# BigBus_Error.net
KiCad netlist of a schematic drawn in EAGLE
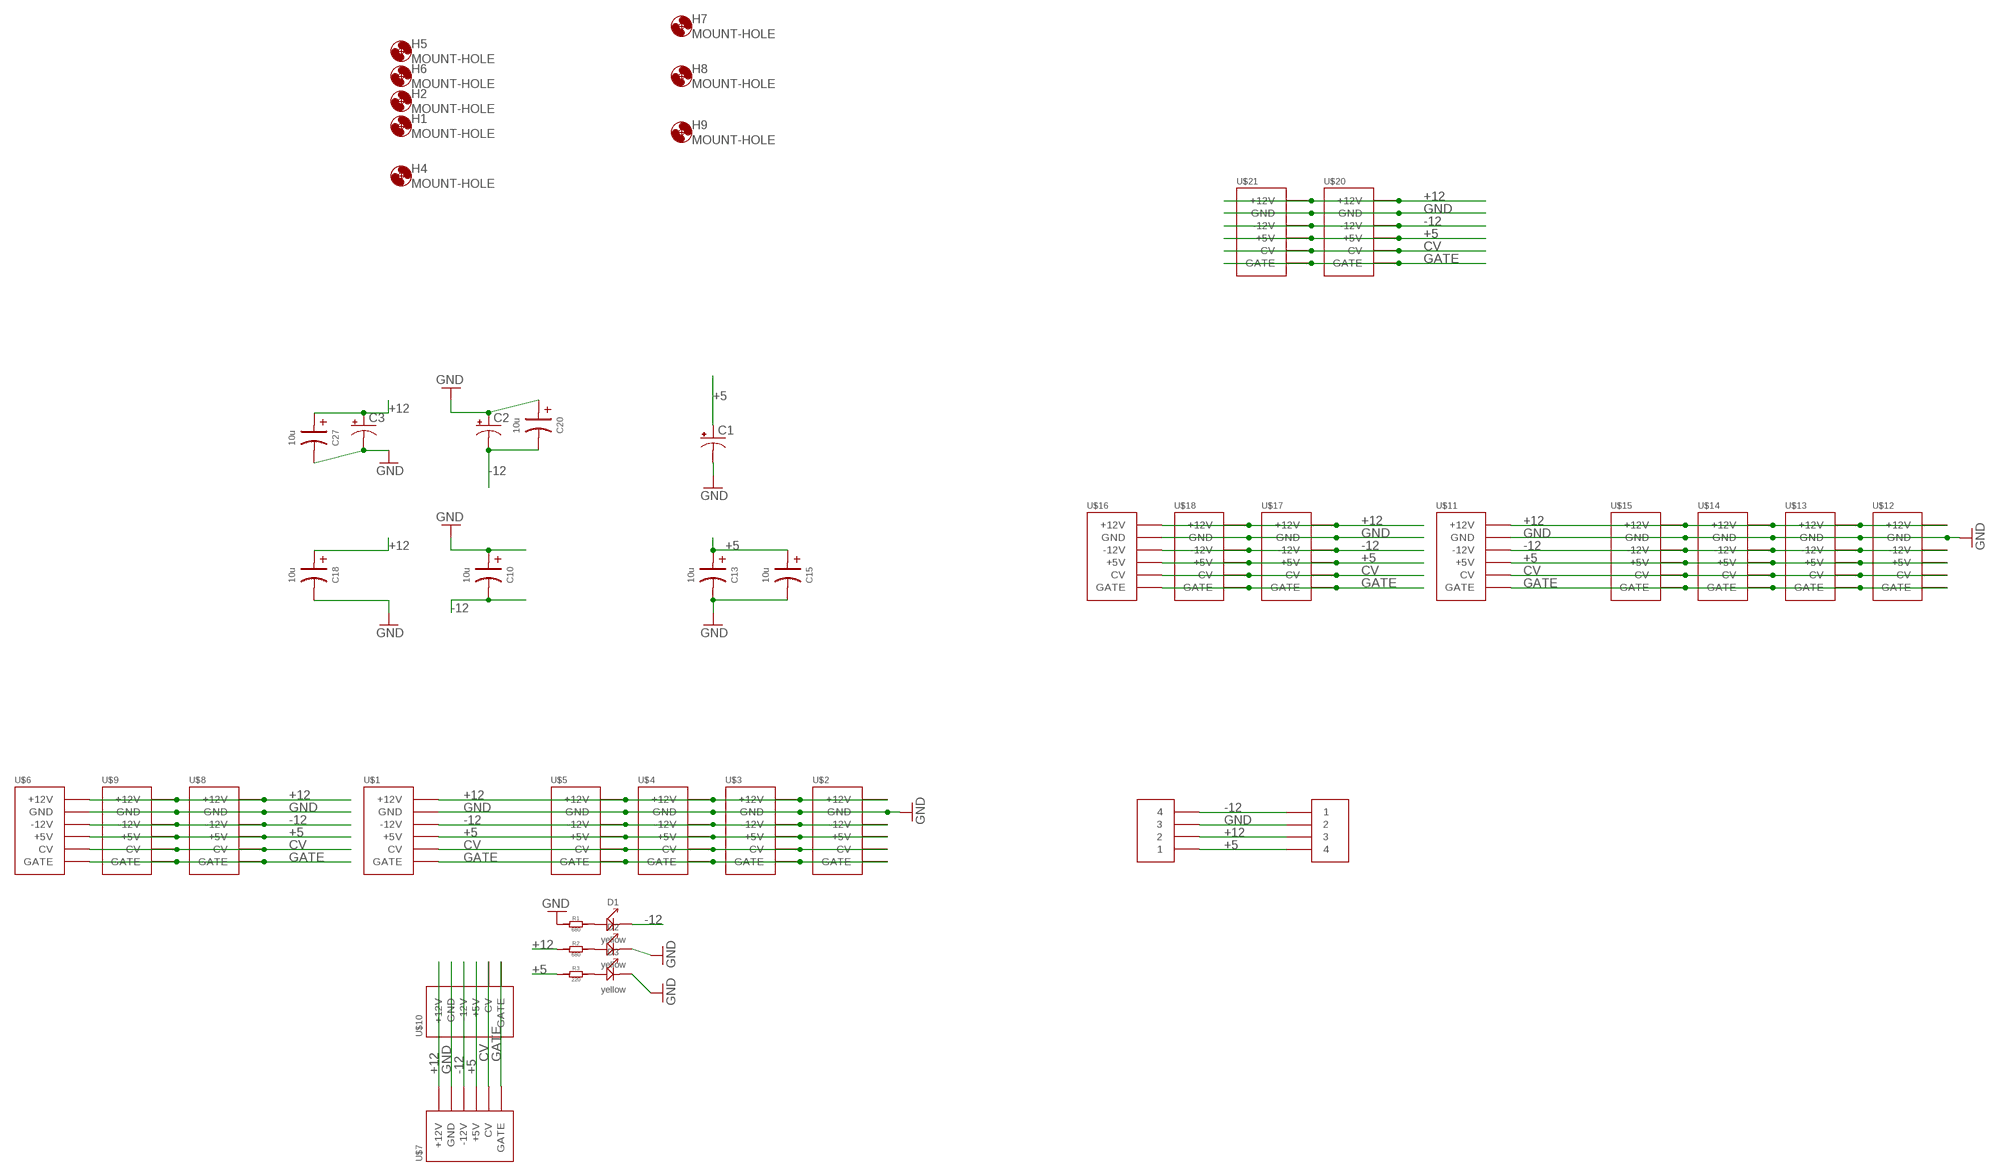
[diagram p0: schematic, sheet 1]

(export (version "E")
  (design (tool "Eeschema 10.0.6"))
  (components
    (comp (ref "C1")
      (value "CAP_POLD")
      (footprint "eagle-import:PANASONIC_D")
      (libsource (lib "eagle-import") (part "CAP_POLD"))
    )
    (comp (ref "C2")
      (value "CAP_POLD")
      (footprint "eagle-import:PANASONIC_D")
      (libsource (lib "eagle-import") (part "CAP_POLD"))
    )
    (comp (ref "C3")
      (value "CAP_POLD")
      (footprint "eagle-import:PANASONIC_D")
      (libsource (lib "eagle-import") (part "CAP_POLD"))
    )
    (comp (ref "C10")
      (value "10u")
      (footprint "eagle-import:AVX-A")
      (libsource (lib "eagle-import") (part "C-POLAR-A"))
    )
    (comp (ref "C13")
      (value "10u")
      (footprint "eagle-import:AVX-A")
      (libsource (lib "eagle-import") (part "C-POLAR-A"))
    )
    (comp (ref "C15")
      (value "10u")
      (footprint "eagle-import:AVX-A")
      (libsource (lib "eagle-import") (part "C-POLAR-A"))
    )
    (comp (ref "C18")
      (value "10u")
      (footprint "eagle-import:AVX-A")
      (libsource (lib "eagle-import") (part "C-POLAR-A"))
    )
    (comp (ref "C20")
      (value "10u")
      (footprint "eagle-import:AVX-A")
      (libsource (lib "eagle-import") (part "C-POLAR-A"))
    )
    (comp (ref "C27")
      (value "10u")
      (footprint "eagle-import:AVX-A")
      (libsource (lib "eagle-import") (part "C-POLAR-A"))
    )
    (comp (ref "D1")
      (value "yellow")
      (footprint "eagle-import:LED0603")
      (libsource (lib "eagle-import") (part "LED"))
    )
    (comp (ref "D2")
      (value "yellow")
      (footprint "eagle-import:LED0603")
      (libsource (lib "eagle-import") (part "LED"))
    )
    (comp (ref "D3")
      (value "yellow")
      (footprint "eagle-import:LED0603")
      (libsource (lib "eagle-import") (part "LED"))
    )
    (comp (ref "H1")
      (value "MOUNT-HOLE")
      (footprint "eagle-import:3.2-NOMARKINGS-SMALLSAFEZONE")
      (libsource (lib "eagle-import") (part "MOUNT-HOLE"))
    )
    (comp (ref "H2")
      (value "MOUNT-HOLE")
      (footprint "eagle-import:3.2-NOMARKINGS-SMALLSAFEZONE")
      (libsource (lib "eagle-import") (part "MOUNT-HOLE"))
    )
    (comp (ref "H4")
      (value "MOUNT-HOLE")
      (footprint "eagle-import:3.2-NOMARKINGS-SMALLSAFEZONE")
      (libsource (lib "eagle-import") (part "MOUNT-HOLE"))
    )
    (comp (ref "H5")
      (value "MOUNT-HOLE")
      (footprint "eagle-import:3.2-NOMARKINGS-SMALLSAFEZONE")
      (libsource (lib "eagle-import") (part "MOUNT-HOLE"))
    )
    (comp (ref "H6")
      (value "MOUNT-HOLE")
      (footprint "eagle-import:3.2-NOMARKINGS-SMALLSAFEZONE")
      (libsource (lib "eagle-import") (part "MOUNT-HOLE"))
    )
    (comp (ref "H7")
      (value "MOUNT-HOLE")
      (footprint "eagle-import:3.2-NOMARKINGS-SMALLSAFEZONE")
      (libsource (lib "eagle-import") (part "MOUNT-HOLE"))
    )
    (comp (ref "H8")
      (value "MOUNT-HOLE")
      (footprint "eagle-import:3.2-NOMARKINGS-SMALLSAFEZONE")
      (libsource (lib "eagle-import") (part "MOUNT-HOLE"))
    )
    (comp (ref "H9")
      (value "MOUNT-HOLE")
      (footprint "eagle-import:3.2-NOMARKINGS-SMALLSAFEZONE")
      (libsource (lib "eagle-import") (part "MOUNT-HOLE"))
    )
    (comp (ref "R1")
      (value "680")
      (footprint "eagle-import:R0603")
      (libsource (lib "eagle-import") (part "R-0603"))
    )
    (comp (ref "R2")
      (value "680")
      (footprint "eagle-import:R0603")
      (libsource (lib "eagle-import") (part "R-0603"))
    )
    (comp (ref "R3")
      (value "220")
      (footprint "eagle-import:R0603")
      (libsource (lib "eagle-import") (part "R-0603"))
    )
    (comp (ref "U$1")
      (value "POWER_SHROUDED_NOTEXT")
      (footprint "eagle-import:POWER_16_SHROUDED_NOTEXT")
      (libsource (lib "eagle-import") (part "POWER_SHROUDED_NOTEXT"))
    )
    (comp (ref "U$2")
      (value "POWER_SHROUDED_NOTEXT")
      (footprint "eagle-import:POWER_16_SHROUDED_NOTEXT")
      (libsource (lib "eagle-import") (part "POWER_SHROUDED_NOTEXT"))
    )
    (comp (ref "U$3")
      (value "POWER_SHROUDED_NOTEXT")
      (footprint "eagle-import:POWER_16_SHROUDED_NOTEXT")
      (libsource (lib "eagle-import") (part "POWER_SHROUDED_NOTEXT"))
    )
    (comp (ref "U$4")
      (value "POWER_SHROUDED_NOTEXT")
      (footprint "eagle-import:POWER_16_SHROUDED_NOTEXT")
      (libsource (lib "eagle-import") (part "POWER_SHROUDED_NOTEXT"))
    )
    (comp (ref "U$5")
      (value "POWER_SHROUDED_NOTEXT")
      (footprint "eagle-import:POWER_16_SHROUDED_NOTEXT")
      (libsource (lib "eagle-import") (part "POWER_SHROUDED_NOTEXT"))
    )
    (comp (ref "U$6")
      (value "POWER_SHROUDED_NOTEXT")
      (footprint "eagle-import:POWER_16_SHROUDED_NOTEXT")
      (libsource (lib "eagle-import") (part "POWER_SHROUDED_NOTEXT"))
    )
    (comp (ref "U$7")
      (value "POWER_SHROUDED_NOTEXT")
      (footprint "eagle-import:POWER_16_SHROUDED_NOTEXT")
      (libsource (lib "eagle-import") (part "POWER_SHROUDED_NOTEXT"))
    )
    (comp (ref "U$8")
      (value "POWER_SHROUDED_NOTEXT")
      (footprint "eagle-import:POWER_16_SHROUDED_NOTEXT")
      (libsource (lib "eagle-import") (part "POWER_SHROUDED_NOTEXT"))
    )
    (comp (ref "U$9")
      (value "POWER_SHROUDED_NOTEXT")
      (footprint "eagle-import:POWER_16_SHROUDED_NOTEXT")
      (libsource (lib "eagle-import") (part "POWER_SHROUDED_NOTEXT"))
    )
    (comp (ref "U$10")
      (value "POWER_SHROUDED_NOTEXT")
      (footprint "eagle-import:POWER_16_SHROUDED_NOTEXT")
      (libsource (lib "eagle-import") (part "POWER_SHROUDED_NOTEXT"))
    )
    (comp (ref "U$11")
      (value "POWER_SHROUDED_NOTEXT")
      (footprint "eagle-import:POWER_16_SHROUDED_NOTEXT")
      (libsource (lib "eagle-import") (part "POWER_SHROUDED_NOTEXT"))
    )
    (comp (ref "U$12")
      (value "POWER_SHROUDED_NOTEXT")
      (footprint "eagle-import:POWER_16_SHROUDED_NOTEXT")
      (libsource (lib "eagle-import") (part "POWER_SHROUDED_NOTEXT"))
    )
    (comp (ref "U$13")
      (value "POWER_SHROUDED_NOTEXT")
      (footprint "eagle-import:POWER_16_SHROUDED_NOTEXT")
      (libsource (lib "eagle-import") (part "POWER_SHROUDED_NOTEXT"))
    )
    (comp (ref "U$14")
      (value "POWER_SHROUDED_NOTEXT")
      (footprint "eagle-import:POWER_16_SHROUDED_NOTEXT")
      (libsource (lib "eagle-import") (part "POWER_SHROUDED_NOTEXT"))
    )
    (comp (ref "U$15")
      (value "POWER_SHROUDED_NOTEXT")
      (footprint "eagle-import:POWER_16_SHROUDED_NOTEXT")
      (libsource (lib "eagle-import") (part "POWER_SHROUDED_NOTEXT"))
    )
    (comp (ref "U$16")
      (value "POWER_SHROUDED_NOTEXT")
      (footprint "eagle-import:POWER_16_SHROUDED_NOTEXT")
      (libsource (lib "eagle-import") (part "POWER_SHROUDED_NOTEXT"))
    )
    (comp (ref "U$17")
      (value "POWER_SHROUDED_NOTEXT")
      (footprint "eagle-import:POWER_16_SHROUDED_NOTEXT")
      (libsource (lib "eagle-import") (part "POWER_SHROUDED_NOTEXT"))
    )
    (comp (ref "U$18")
      (value "POWER_SHROUDED_NOTEXT")
      (footprint "eagle-import:POWER_16_SHROUDED_NOTEXT")
      (libsource (lib "eagle-import") (part "POWER_SHROUDED_NOTEXT"))
    )
    (comp (ref "U$19")
      (value "4PIN5MM")
      (footprint "eagle-import:4PIN5MM")
      (libsource (lib "eagle-import") (part "4PIN5MM"))
    )
    (comp (ref "U$20")
      (value "POWER_SHROUDED_NOTEXT")
      (footprint "eagle-import:POWER_16_SHROUDED_NOTEXT")
      (libsource (lib "eagle-import") (part "POWER_SHROUDED_NOTEXT"))
    )
    (comp (ref "U$21")
      (value "POWER_SHROUDED_NOTEXT")
      (footprint "eagle-import:POWER_16_SHROUDED_NOTEXT")
      (libsource (lib "eagle-import") (part "POWER_SHROUDED_NOTEXT"))
    )
    (comp (ref "U$22")
      (value "4PIN5MM")
      (footprint "eagle-import:4PIN5MM")
      (libsource (lib "eagle-import") (part "4PIN5MM"))
    )
  )
  (nets
    (net (code "1") (name "/+5") (class "Default")
      (node (ref "C1") (pin "+") (pinfunction "+_+") (pintype "passive"))
      (node (ref "C13") (pin "+") (pinfunction "1_+") (pintype "bidirectional"))
      (node (ref "C15") (pin "+") (pinfunction "1_+") (pintype "bidirectional"))
      (node (ref "R3") (pin "1") (pinfunction "1_1") (pintype "bidirectional"))
      (node (ref "U$1") (pin "11") (pinfunction "+5V_11") (pintype "bidirectional"))
      (node (ref "U$1") (pin "12") (pinfunction "+5V_12") (pintype "bidirectional"))
      (node (ref "U$10") (pin "11") (pinfunction "+5V_11") (pintype "bidirectional"))
      (node (ref "U$10") (pin "12") (pinfunction "+5V_12") (pintype "bidirectional"))
      (node (ref "U$11") (pin "11") (pinfunction "+5V_11") (pintype "bidirectional"))
      (node (ref "U$11") (pin "12") (pinfunction "+5V_12") (pintype "bidirectional"))
      (node (ref "U$12") (pin "11") (pinfunction "+5V_11") (pintype "bidirectional"))
      (node (ref "U$12") (pin "12") (pinfunction "+5V_12") (pintype "bidirectional"))
      (node (ref "U$13") (pin "11") (pinfunction "+5V_11") (pintype "bidirectional"))
      (node (ref "U$13") (pin "12") (pinfunction "+5V_12") (pintype "bidirectional"))
      (node (ref "U$14") (pin "11") (pinfunction "+5V_11") (pintype "bidirectional"))
      (node (ref "U$14") (pin "12") (pinfunction "+5V_12") (pintype "bidirectional"))
      (node (ref "U$15") (pin "11") (pinfunction "+5V_11") (pintype "bidirectional"))
      (node (ref "U$15") (pin "12") (pinfunction "+5V_12") (pintype "bidirectional"))
      (node (ref "U$16") (pin "11") (pinfunction "+5V_11") (pintype "bidirectional"))
      (node (ref "U$16") (pin "12") (pinfunction "+5V_12") (pintype "bidirectional"))
      (node (ref "U$17") (pin "11") (pinfunction "+5V_11") (pintype "bidirectional"))
      (node (ref "U$17") (pin "12") (pinfunction "+5V_12") (pintype "bidirectional"))
      (node (ref "U$18") (pin "11") (pinfunction "+5V_11") (pintype "bidirectional"))
      (node (ref "U$18") (pin "12") (pinfunction "+5V_12") (pintype "bidirectional"))
      (node (ref "U$19") (pin "4") (pinfunction "4_4") (pintype "bidirectional"))
      (node (ref "U$2") (pin "11") (pinfunction "+5V_11") (pintype "bidirectional"))
      (node (ref "U$2") (pin "12") (pinfunction "+5V_12") (pintype "bidirectional"))
      (node (ref "U$20") (pin "11") (pinfunction "+5V_11") (pintype "bidirectional"))
      (node (ref "U$20") (pin "12") (pinfunction "+5V_12") (pintype "bidirectional"))
      (node (ref "U$21") (pin "11") (pinfunction "+5V_11") (pintype "bidirectional"))
      (node (ref "U$21") (pin "12") (pinfunction "+5V_12") (pintype "bidirectional"))
      (node (ref "U$22") (pin "1") (pinfunction "1_1") (pintype "bidirectional"))
      (node (ref "U$3") (pin "11") (pinfunction "+5V_11") (pintype "bidirectional"))
      (node (ref "U$3") (pin "12") (pinfunction "+5V_12") (pintype "bidirectional"))
      (node (ref "U$4") (pin "11") (pinfunction "+5V_11") (pintype "bidirectional"))
      (node (ref "U$4") (pin "12") (pinfunction "+5V_12") (pintype "bidirectional"))
      (node (ref "U$5") (pin "11") (pinfunction "+5V_11") (pintype "bidirectional"))
      (node (ref "U$5") (pin "12") (pinfunction "+5V_12") (pintype "bidirectional"))
      (node (ref "U$6") (pin "11") (pinfunction "+5V_11") (pintype "bidirectional"))
      (node (ref "U$6") (pin "12") (pinfunction "+5V_12") (pintype "bidirectional"))
      (node (ref "U$7") (pin "11") (pinfunction "+5V_11") (pintype "bidirectional"))
      (node (ref "U$7") (pin "12") (pinfunction "+5V_12") (pintype "bidirectional"))
      (node (ref "U$8") (pin "11") (pinfunction "+5V_11") (pintype "bidirectional"))
      (node (ref "U$8") (pin "12") (pinfunction "+5V_12") (pintype "bidirectional"))
      (node (ref "U$9") (pin "11") (pinfunction "+5V_11") (pintype "bidirectional"))
      (node (ref "U$9") (pin "12") (pinfunction "+5V_12") (pintype "bidirectional"))
    )
    (net (code "2") (name "/+12") (class "Default")
      (node (ref "C18") (pin "+") (pinfunction "1_+") (pintype "bidirectional"))
      (node (ref "C27") (pin "+") (pinfunction "1_+") (pintype "bidirectional"))
      (node (ref "C3") (pin "+") (pinfunction "+_+") (pintype "passive"))
      (node (ref "R2") (pin "1") (pinfunction "1_1") (pintype "bidirectional"))
      (node (ref "U$1") (pin "10") (pinfunction "+12V_10") (pintype "bidirectional"))
      (node (ref "U$1") (pin "9") (pinfunction "+12V_9") (pintype "bidirectional"))
      (node (ref "U$10") (pin "10") (pinfunction "+12V_10") (pintype "bidirectional"))
      (node (ref "U$10") (pin "9") (pinfunction "+12V_9") (pintype "bidirectional"))
      (node (ref "U$11") (pin "10") (pinfunction "+12V_10") (pintype "bidirectional"))
      (node (ref "U$11") (pin "9") (pinfunction "+12V_9") (pintype "bidirectional"))
      (node (ref "U$12") (pin "10") (pinfunction "+12V_10") (pintype "bidirectional"))
      (node (ref "U$12") (pin "9") (pinfunction "+12V_9") (pintype "bidirectional"))
      (node (ref "U$13") (pin "10") (pinfunction "+12V_10") (pintype "bidirectional"))
      (node (ref "U$13") (pin "9") (pinfunction "+12V_9") (pintype "bidirectional"))
      (node (ref "U$14") (pin "10") (pinfunction "+12V_10") (pintype "bidirectional"))
      (node (ref "U$14") (pin "9") (pinfunction "+12V_9") (pintype "bidirectional"))
      (node (ref "U$15") (pin "10") (pinfunction "+12V_10") (pintype "bidirectional"))
      (node (ref "U$15") (pin "9") (pinfunction "+12V_9") (pintype "bidirectional"))
      (node (ref "U$16") (pin "10") (pinfunction "+12V_10") (pintype "bidirectional"))
      (node (ref "U$16") (pin "9") (pinfunction "+12V_9") (pintype "bidirectional"))
      (node (ref "U$17") (pin "10") (pinfunction "+12V_10") (pintype "bidirectional"))
      (node (ref "U$17") (pin "9") (pinfunction "+12V_9") (pintype "bidirectional"))
      (node (ref "U$18") (pin "10") (pinfunction "+12V_10") (pintype "bidirectional"))
      (node (ref "U$18") (pin "9") (pinfunction "+12V_9") (pintype "bidirectional"))
      (node (ref "U$19") (pin "3") (pinfunction "3_3") (pintype "bidirectional"))
      (node (ref "U$2") (pin "10") (pinfunction "+12V_10") (pintype "bidirectional"))
      (node (ref "U$2") (pin "9") (pinfunction "+12V_9") (pintype "bidirectional"))
      (node (ref "U$20") (pin "10") (pinfunction "+12V_10") (pintype "bidirectional"))
      (node (ref "U$20") (pin "9") (pinfunction "+12V_9") (pintype "bidirectional"))
      (node (ref "U$21") (pin "10") (pinfunction "+12V_10") (pintype "bidirectional"))
      (node (ref "U$21") (pin "9") (pinfunction "+12V_9") (pintype "bidirectional"))
      (node (ref "U$22") (pin "2") (pinfunction "2_2") (pintype "bidirectional"))
      (node (ref "U$3") (pin "10") (pinfunction "+12V_10") (pintype "bidirectional"))
      (node (ref "U$3") (pin "9") (pinfunction "+12V_9") (pintype "bidirectional"))
      (node (ref "U$4") (pin "10") (pinfunction "+12V_10") (pintype "bidirectional"))
      (node (ref "U$4") (pin "9") (pinfunction "+12V_9") (pintype "bidirectional"))
      (node (ref "U$5") (pin "10") (pinfunction "+12V_10") (pintype "bidirectional"))
      (node (ref "U$5") (pin "9") (pinfunction "+12V_9") (pintype "bidirectional"))
      (node (ref "U$6") (pin "10") (pinfunction "+12V_10") (pintype "bidirectional"))
      (node (ref "U$6") (pin "9") (pinfunction "+12V_9") (pintype "bidirectional"))
      (node (ref "U$7") (pin "10") (pinfunction "+12V_10") (pintype "bidirectional"))
      (node (ref "U$7") (pin "9") (pinfunction "+12V_9") (pintype "bidirectional"))
      (node (ref "U$8") (pin "10") (pinfunction "+12V_10") (pintype "bidirectional"))
      (node (ref "U$8") (pin "9") (pinfunction "+12V_9") (pintype "bidirectional"))
      (node (ref "U$9") (pin "10") (pinfunction "+12V_10") (pintype "bidirectional"))
      (node (ref "U$9") (pin "9") (pinfunction "+12V_9") (pintype "bidirectional"))
    )
    (net (code "3") (name "/-12") (class "Default")
      (node (ref "C10") (pin "-") (pinfunction "2_-") (pintype "bidirectional"))
      (node (ref "C2") (pin "-") (pinfunction "-_-") (pintype "passive"))
      (node (ref "C20") (pin "-") (pinfunction "2_-") (pintype "bidirectional"))
      (node (ref "D1") (pin "-") (pinfunction "-_-") (pintype "passive"))
      (node (ref "U$1") (pin "1") (pinfunction "-12V_1") (pintype "bidirectional"))
      (node (ref "U$1") (pin "2") (pinfunction "-12V_2") (pintype "bidirectional"))
      (node (ref "U$10") (pin "1") (pinfunction "-12V_1") (pintype "bidirectional"))
      (node (ref "U$10") (pin "2") (pinfunction "-12V_2") (pintype "bidirectional"))
      (node (ref "U$11") (pin "1") (pinfunction "-12V_1") (pintype "bidirectional"))
      (node (ref "U$11") (pin "2") (pinfunction "-12V_2") (pintype "bidirectional"))
      (node (ref "U$12") (pin "1") (pinfunction "-12V_1") (pintype "bidirectional"))
      (node (ref "U$12") (pin "2") (pinfunction "-12V_2") (pintype "bidirectional"))
      (node (ref "U$13") (pin "1") (pinfunction "-12V_1") (pintype "bidirectional"))
      (node (ref "U$13") (pin "2") (pinfunction "-12V_2") (pintype "bidirectional"))
      (node (ref "U$14") (pin "1") (pinfunction "-12V_1") (pintype "bidirectional"))
      (node (ref "U$14") (pin "2") (pinfunction "-12V_2") (pintype "bidirectional"))
      (node (ref "U$15") (pin "1") (pinfunction "-12V_1") (pintype "bidirectional"))
      (node (ref "U$15") (pin "2") (pinfunction "-12V_2") (pintype "bidirectional"))
      (node (ref "U$16") (pin "1") (pinfunction "-12V_1") (pintype "bidirectional"))
      (node (ref "U$16") (pin "2") (pinfunction "-12V_2") (pintype "bidirectional"))
      (node (ref "U$17") (pin "1") (pinfunction "-12V_1") (pintype "bidirectional"))
      (node (ref "U$17") (pin "2") (pinfunction "-12V_2") (pintype "bidirectional"))
      (node (ref "U$18") (pin "1") (pinfunction "-12V_1") (pintype "bidirectional"))
      (node (ref "U$18") (pin "2") (pinfunction "-12V_2") (pintype "bidirectional"))
      (node (ref "U$19") (pin "1") (pinfunction "1_1") (pintype "bidirectional"))
      (node (ref "U$2") (pin "1") (pinfunction "-12V_1") (pintype "bidirectional"))
      (node (ref "U$2") (pin "2") (pinfunction "-12V_2") (pintype "bidirectional"))
      (node (ref "U$20") (pin "1") (pinfunction "-12V_1") (pintype "bidirectional"))
      (node (ref "U$20") (pin "2") (pinfunction "-12V_2") (pintype "bidirectional"))
      (node (ref "U$21") (pin "1") (pinfunction "-12V_1") (pintype "bidirectional"))
      (node (ref "U$21") (pin "2") (pinfunction "-12V_2") (pintype "bidirectional"))
      (node (ref "U$22") (pin "4") (pinfunction "4_4") (pintype "bidirectional"))
      (node (ref "U$3") (pin "1") (pinfunction "-12V_1") (pintype "bidirectional"))
      (node (ref "U$3") (pin "2") (pinfunction "-12V_2") (pintype "bidirectional"))
      (node (ref "U$4") (pin "1") (pinfunction "-12V_1") (pintype "bidirectional"))
      (node (ref "U$4") (pin "2") (pinfunction "-12V_2") (pintype "bidirectional"))
      (node (ref "U$5") (pin "1") (pinfunction "-12V_1") (pintype "bidirectional"))
      (node (ref "U$5") (pin "2") (pinfunction "-12V_2") (pintype "bidirectional"))
      (node (ref "U$6") (pin "1") (pinfunction "-12V_1") (pintype "bidirectional"))
      (node (ref "U$6") (pin "2") (pinfunction "-12V_2") (pintype "bidirectional"))
      (node (ref "U$7") (pin "1") (pinfunction "-12V_1") (pintype "bidirectional"))
      (node (ref "U$7") (pin "2") (pinfunction "-12V_2") (pintype "bidirectional"))
      (node (ref "U$8") (pin "1") (pinfunction "-12V_1") (pintype "bidirectional"))
      (node (ref "U$8") (pin "2") (pinfunction "-12V_2") (pintype "bidirectional"))
      (node (ref "U$9") (pin "1") (pinfunction "-12V_1") (pintype "bidirectional"))
      (node (ref "U$9") (pin "2") (pinfunction "-12V_2") (pintype "bidirectional"))
    )
    (net (code "4") (name "/CV") (class "Default")
      (node (ref "U$1") (pin "13") (pinfunction "CV_13") (pintype "bidirectional"))
      (node (ref "U$1") (pin "14") (pinfunction "CV_14") (pintype "bidirectional"))
      (node (ref "U$10") (pin "13") (pinfunction "CV_13") (pintype "bidirectional"))
      (node (ref "U$10") (pin "14") (pinfunction "CV_14") (pintype "bidirectional"))
      (node (ref "U$11") (pin "13") (pinfunction "CV_13") (pintype "bidirectional"))
      (node (ref "U$11") (pin "14") (pinfunction "CV_14") (pintype "bidirectional"))
      (node (ref "U$12") (pin "13") (pinfunction "CV_13") (pintype "bidirectional"))
      (node (ref "U$12") (pin "14") (pinfunction "CV_14") (pintype "bidirectional"))
      (node (ref "U$13") (pin "13") (pinfunction "CV_13") (pintype "bidirectional"))
      (node (ref "U$13") (pin "14") (pinfunction "CV_14") (pintype "bidirectional"))
      (node (ref "U$14") (pin "13") (pinfunction "CV_13") (pintype "bidirectional"))
      (node (ref "U$14") (pin "14") (pinfunction "CV_14") (pintype "bidirectional"))
      (node (ref "U$15") (pin "13") (pinfunction "CV_13") (pintype "bidirectional"))
      (node (ref "U$15") (pin "14") (pinfunction "CV_14") (pintype "bidirectional"))
      (node (ref "U$16") (pin "13") (pinfunction "CV_13") (pintype "bidirectional"))
      (node (ref "U$16") (pin "14") (pinfunction "CV_14") (pintype "bidirectional"))
      (node (ref "U$17") (pin "13") (pinfunction "CV_13") (pintype "bidirectional"))
      (node (ref "U$17") (pin "14") (pinfunction "CV_14") (pintype "bidirectional"))
      (node (ref "U$18") (pin "13") (pinfunction "CV_13") (pintype "bidirectional"))
      (node (ref "U$18") (pin "14") (pinfunction "CV_14") (pintype "bidirectional"))
      (node (ref "U$2") (pin "13") (pinfunction "CV_13") (pintype "bidirectional"))
      (node (ref "U$2") (pin "14") (pinfunction "CV_14") (pintype "bidirectional"))
      (node (ref "U$20") (pin "13") (pinfunction "CV_13") (pintype "bidirectional"))
      (node (ref "U$20") (pin "14") (pinfunction "CV_14") (pintype "bidirectional"))
      (node (ref "U$21") (pin "13") (pinfunction "CV_13") (pintype "bidirectional"))
      (node (ref "U$21") (pin "14") (pinfunction "CV_14") (pintype "bidirectional"))
      (node (ref "U$3") (pin "13") (pinfunction "CV_13") (pintype "bidirectional"))
      (node (ref "U$3") (pin "14") (pinfunction "CV_14") (pintype "bidirectional"))
      (node (ref "U$4") (pin "13") (pinfunction "CV_13") (pintype "bidirectional"))
      (node (ref "U$4") (pin "14") (pinfunction "CV_14") (pintype "bidirectional"))
      (node (ref "U$5") (pin "13") (pinfunction "CV_13") (pintype "bidirectional"))
      (node (ref "U$5") (pin "14") (pinfunction "CV_14") (pintype "bidirectional"))
      (node (ref "U$6") (pin "13") (pinfunction "CV_13") (pintype "bidirectional"))
      (node (ref "U$6") (pin "14") (pinfunction "CV_14") (pintype "bidirectional"))
      (node (ref "U$7") (pin "13") (pinfunction "CV_13") (pintype "bidirectional"))
      (node (ref "U$7") (pin "14") (pinfunction "CV_14") (pintype "bidirectional"))
      (node (ref "U$8") (pin "13") (pinfunction "CV_13") (pintype "bidirectional"))
      (node (ref "U$8") (pin "14") (pinfunction "CV_14") (pintype "bidirectional"))
      (node (ref "U$9") (pin "13") (pinfunction "CV_13") (pintype "bidirectional"))
      (node (ref "U$9") (pin "14") (pinfunction "CV_14") (pintype "bidirectional"))
    )
    (net (code "5") (name "/GATE") (class "Default")
      (node (ref "U$1") (pin "15") (pinfunction "GATE_15") (pintype "bidirectional"))
      (node (ref "U$1") (pin "16") (pinfunction "GATE_16") (pintype "bidirectional"))
      (node (ref "U$10") (pin "15") (pinfunction "GATE_15") (pintype "bidirectional"))
      (node (ref "U$10") (pin "16") (pinfunction "GATE_16") (pintype "bidirectional"))
      (node (ref "U$11") (pin "15") (pinfunction "GATE_15") (pintype "bidirectional"))
      (node (ref "U$11") (pin "16") (pinfunction "GATE_16") (pintype "bidirectional"))
      (node (ref "U$12") (pin "15") (pinfunction "GATE_15") (pintype "bidirectional"))
      (node (ref "U$12") (pin "16") (pinfunction "GATE_16") (pintype "bidirectional"))
      (node (ref "U$13") (pin "15") (pinfunction "GATE_15") (pintype "bidirectional"))
      (node (ref "U$13") (pin "16") (pinfunction "GATE_16") (pintype "bidirectional"))
      (node (ref "U$14") (pin "15") (pinfunction "GATE_15") (pintype "bidirectional"))
      (node (ref "U$14") (pin "16") (pinfunction "GATE_16") (pintype "bidirectional"))
      (node (ref "U$15") (pin "15") (pinfunction "GATE_15") (pintype "bidirectional"))
      (node (ref "U$15") (pin "16") (pinfunction "GATE_16") (pintype "bidirectional"))
      (node (ref "U$16") (pin "15") (pinfunction "GATE_15") (pintype "bidirectional"))
      (node (ref "U$16") (pin "16") (pinfunction "GATE_16") (pintype "bidirectional"))
      (node (ref "U$17") (pin "15") (pinfunction "GATE_15") (pintype "bidirectional"))
      (node (ref "U$17") (pin "16") (pinfunction "GATE_16") (pintype "bidirectional"))
      (node (ref "U$18") (pin "15") (pinfunction "GATE_15") (pintype "bidirectional"))
      (node (ref "U$18") (pin "16") (pinfunction "GATE_16") (pintype "bidirectional"))
      (node (ref "U$2") (pin "15") (pinfunction "GATE_15") (pintype "bidirectional"))
      (node (ref "U$2") (pin "16") (pinfunction "GATE_16") (pintype "bidirectional"))
      (node (ref "U$20") (pin "15") (pinfunction "GATE_15") (pintype "bidirectional"))
      (node (ref "U$20") (pin "16") (pinfunction "GATE_16") (pintype "bidirectional"))
      (node (ref "U$21") (pin "15") (pinfunction "GATE_15") (pintype "bidirectional"))
      (node (ref "U$21") (pin "16") (pinfunction "GATE_16") (pintype "bidirectional"))
      (node (ref "U$3") (pin "15") (pinfunction "GATE_15") (pintype "bidirectional"))
      (node (ref "U$3") (pin "16") (pinfunction "GATE_16") (pintype "bidirectional"))
      (node (ref "U$4") (pin "15") (pinfunction "GATE_15") (pintype "bidirectional"))
      (node (ref "U$4") (pin "16") (pinfunction "GATE_16") (pintype "bidirectional"))
      (node (ref "U$5") (pin "15") (pinfunction "GATE_15") (pintype "bidirectional"))
      (node (ref "U$5") (pin "16") (pinfunction "GATE_16") (pintype "bidirectional"))
      (node (ref "U$6") (pin "15") (pinfunction "GATE_15") (pintype "bidirectional"))
      (node (ref "U$6") (pin "16") (pinfunction "GATE_16") (pintype "bidirectional"))
      (node (ref "U$7") (pin "15") (pinfunction "GATE_15") (pintype "bidirectional"))
      (node (ref "U$7") (pin "16") (pinfunction "GATE_16") (pintype "bidirectional"))
      (node (ref "U$8") (pin "15") (pinfunction "GATE_15") (pintype "bidirectional"))
      (node (ref "U$8") (pin "16") (pinfunction "GATE_16") (pintype "bidirectional"))
      (node (ref "U$9") (pin "15") (pinfunction "GATE_15") (pintype "bidirectional"))
      (node (ref "U$9") (pin "16") (pinfunction "GATE_16") (pintype "bidirectional"))
    )
    (net (code "6") (name "GND") (class "Default")
      (node (ref "C1") (pin "-") (pinfunction "-_-") (pintype "passive"))
      (node (ref "C10") (pin "+") (pinfunction "1_+") (pintype "bidirectional"))
      (node (ref "C13") (pin "-") (pinfunction "2_-") (pintype "bidirectional"))
      (node (ref "C15") (pin "-") (pinfunction "2_-") (pintype "bidirectional"))
      (node (ref "C18") (pin "-") (pinfunction "2_-") (pintype "bidirectional"))
      (node (ref "C2") (pin "+") (pinfunction "+_+") (pintype "passive"))
      (node (ref "C20") (pin "+") (pinfunction "1_+") (pintype "bidirectional"))
      (node (ref "C27") (pin "-") (pinfunction "2_-") (pintype "bidirectional"))
      (node (ref "C3") (pin "-") (pinfunction "-_-") (pintype "passive"))
      (node (ref "D2") (pin "-") (pinfunction "-_-") (pintype "passive"))
      (node (ref "D3") (pin "-") (pinfunction "-_-") (pintype "passive"))
      (node (ref "R1") (pin "1") (pinfunction "1_1") (pintype "bidirectional"))
      (node (ref "U$1") (pin "3") (pinfunction "GND_3") (pintype "bidirectional"))
      (node (ref "U$1") (pin "4") (pinfunction "GND_4") (pintype "bidirectional"))
      (node (ref "U$1") (pin "5") (pinfunction "GND_5") (pintype "bidirectional"))
      (node (ref "U$1") (pin "6") (pinfunction "GND_6") (pintype "bidirectional"))
      (node (ref "U$1") (pin "7") (pinfunction "GND_7") (pintype "bidirectional"))
      (node (ref "U$1") (pin "8") (pinfunction "GND_8") (pintype "bidirectional"))
      (node (ref "U$10") (pin "3") (pinfunction "GND_3") (pintype "bidirectional"))
      (node (ref "U$10") (pin "4") (pinfunction "GND_4") (pintype "bidirectional"))
      (node (ref "U$10") (pin "5") (pinfunction "GND_5") (pintype "bidirectional"))
      (node (ref "U$10") (pin "6") (pinfunction "GND_6") (pintype "bidirectional"))
      (node (ref "U$10") (pin "7") (pinfunction "GND_7") (pintype "bidirectional"))
      (node (ref "U$10") (pin "8") (pinfunction "GND_8") (pintype "bidirectional"))
      (node (ref "U$11") (pin "3") (pinfunction "GND_3") (pintype "bidirectional"))
      (node (ref "U$11") (pin "4") (pinfunction "GND_4") (pintype "bidirectional"))
      (node (ref "U$11") (pin "5") (pinfunction "GND_5") (pintype "bidirectional"))
      (node (ref "U$11") (pin "6") (pinfunction "GND_6") (pintype "bidirectional"))
      (node (ref "U$11") (pin "7") (pinfunction "GND_7") (pintype "bidirectional"))
      (node (ref "U$11") (pin "8") (pinfunction "GND_8") (pintype "bidirectional"))
      (node (ref "U$12") (pin "3") (pinfunction "GND_3") (pintype "bidirectional"))
      (node (ref "U$12") (pin "4") (pinfunction "GND_4") (pintype "bidirectional"))
      (node (ref "U$12") (pin "5") (pinfunction "GND_5") (pintype "bidirectional"))
      (node (ref "U$12") (pin "6") (pinfunction "GND_6") (pintype "bidirectional"))
      (node (ref "U$12") (pin "7") (pinfunction "GND_7") (pintype "bidirectional"))
      (node (ref "U$12") (pin "8") (pinfunction "GND_8") (pintype "bidirectional"))
      (node (ref "U$13") (pin "3") (pinfunction "GND_3") (pintype "bidirectional"))
      (node (ref "U$13") (pin "4") (pinfunction "GND_4") (pintype "bidirectional"))
      (node (ref "U$13") (pin "5") (pinfunction "GND_5") (pintype "bidirectional"))
      (node (ref "U$13") (pin "6") (pinfunction "GND_6") (pintype "bidirectional"))
      (node (ref "U$13") (pin "7") (pinfunction "GND_7") (pintype "bidirectional"))
      (node (ref "U$13") (pin "8") (pinfunction "GND_8") (pintype "bidirectional"))
      (node (ref "U$14") (pin "3") (pinfunction "GND_3") (pintype "bidirectional"))
      (node (ref "U$14") (pin "4") (pinfunction "GND_4") (pintype "bidirectional"))
      (node (ref "U$14") (pin "5") (pinfunction "GND_5") (pintype "bidirectional"))
      (node (ref "U$14") (pin "6") (pinfunction "GND_6") (pintype "bidirectional"))
      (node (ref "U$14") (pin "7") (pinfunction "GND_7") (pintype "bidirectional"))
      (node (ref "U$14") (pin "8") (pinfunction "GND_8") (pintype "bidirectional"))
      (node (ref "U$15") (pin "3") (pinfunction "GND_3") (pintype "bidirectional"))
      (node (ref "U$15") (pin "4") (pinfunction "GND_4") (pintype "bidirectional"))
      (node (ref "U$15") (pin "5") (pinfunction "GND_5") (pintype "bidirectional"))
      (node (ref "U$15") (pin "6") (pinfunction "GND_6") (pintype "bidirectional"))
      (node (ref "U$15") (pin "7") (pinfunction "GND_7") (pintype "bidirectional"))
      (node (ref "U$15") (pin "8") (pinfunction "GND_8") (pintype "bidirectional"))
      (node (ref "U$16") (pin "3") (pinfunction "GND_3") (pintype "bidirectional"))
      (node (ref "U$16") (pin "4") (pinfunction "GND_4") (pintype "bidirectional"))
      (node (ref "U$16") (pin "5") (pinfunction "GND_5") (pintype "bidirectional"))
      (node (ref "U$16") (pin "6") (pinfunction "GND_6") (pintype "bidirectional"))
      (node (ref "U$16") (pin "7") (pinfunction "GND_7") (pintype "bidirectional"))
      (node (ref "U$16") (pin "8") (pinfunction "GND_8") (pintype "bidirectional"))
      (node (ref "U$17") (pin "3") (pinfunction "GND_3") (pintype "bidirectional"))
      (node (ref "U$17") (pin "4") (pinfunction "GND_4") (pintype "bidirectional"))
      (node (ref "U$17") (pin "5") (pinfunction "GND_5") (pintype "bidirectional"))
      (node (ref "U$17") (pin "6") (pinfunction "GND_6") (pintype "bidirectional"))
      (node (ref "U$17") (pin "7") (pinfunction "GND_7") (pintype "bidirectional"))
      (node (ref "U$17") (pin "8") (pinfunction "GND_8") (pintype "bidirectional"))
      (node (ref "U$18") (pin "3") (pinfunction "GND_3") (pintype "bidirectional"))
      (node (ref "U$18") (pin "4") (pinfunction "GND_4") (pintype "bidirectional"))
      (node (ref "U$18") (pin "5") (pinfunction "GND_5") (pintype "bidirectional"))
      (node (ref "U$18") (pin "6") (pinfunction "GND_6") (pintype "bidirectional"))
      (node (ref "U$18") (pin "7") (pinfunction "GND_7") (pintype "bidirectional"))
      (node (ref "U$18") (pin "8") (pinfunction "GND_8") (pintype "bidirectional"))
      (node (ref "U$19") (pin "2") (pinfunction "2_2") (pintype "bidirectional"))
      (node (ref "U$2") (pin "3") (pinfunction "GND_3") (pintype "bidirectional"))
      (node (ref "U$2") (pin "4") (pinfunction "GND_4") (pintype "bidirectional"))
      (node (ref "U$2") (pin "5") (pinfunction "GND_5") (pintype "bidirectional"))
      (node (ref "U$2") (pin "6") (pinfunction "GND_6") (pintype "bidirectional"))
      (node (ref "U$2") (pin "7") (pinfunction "GND_7") (pintype "bidirectional"))
      (node (ref "U$2") (pin "8") (pinfunction "GND_8") (pintype "bidirectional"))
      (node (ref "U$20") (pin "3") (pinfunction "GND_3") (pintype "bidirectional"))
      (node (ref "U$20") (pin "4") (pinfunction "GND_4") (pintype "bidirectional"))
      (node (ref "U$20") (pin "5") (pinfunction "GND_5") (pintype "bidirectional"))
      (node (ref "U$20") (pin "6") (pinfunction "GND_6") (pintype "bidirectional"))
      (node (ref "U$20") (pin "7") (pinfunction "GND_7") (pintype "bidirectional"))
      (node (ref "U$20") (pin "8") (pinfunction "GND_8") (pintype "bidirectional"))
      (node (ref "U$21") (pin "3") (pinfunction "GND_3") (pintype "bidirectional"))
      (node (ref "U$21") (pin "4") (pinfunction "GND_4") (pintype "bidirectional"))
      (node (ref "U$21") (pin "5") (pinfunction "GND_5") (pintype "bidirectional"))
      (node (ref "U$21") (pin "6") (pinfunction "GND_6") (pintype "bidirectional"))
      (node (ref "U$21") (pin "7") (pinfunction "GND_7") (pintype "bidirectional"))
      (node (ref "U$21") (pin "8") (pinfunction "GND_8") (pintype "bidirectional"))
      (node (ref "U$22") (pin "3") (pinfunction "3_3") (pintype "bidirectional"))
      (node (ref "U$3") (pin "3") (pinfunction "GND_3") (pintype "bidirectional"))
      (node (ref "U$3") (pin "4") (pinfunction "GND_4") (pintype "bidirectional"))
      (node (ref "U$3") (pin "5") (pinfunction "GND_5") (pintype "bidirectional"))
      (node (ref "U$3") (pin "6") (pinfunction "GND_6") (pintype "bidirectional"))
      (node (ref "U$3") (pin "7") (pinfunction "GND_7") (pintype "bidirectional"))
      (node (ref "U$3") (pin "8") (pinfunction "GND_8") (pintype "bidirectional"))
      (node (ref "U$4") (pin "3") (pinfunction "GND_3") (pintype "bidirectional"))
      (node (ref "U$4") (pin "4") (pinfunction "GND_4") (pintype "bidirectional"))
      (node (ref "U$4") (pin "5") (pinfunction "GND_5") (pintype "bidirectional"))
      (node (ref "U$4") (pin "6") (pinfunction "GND_6") (pintype "bidirectional"))
      (node (ref "U$4") (pin "7") (pinfunction "GND_7") (pintype "bidirectional"))
      (node (ref "U$4") (pin "8") (pinfunction "GND_8") (pintype "bidirectional"))
      (node (ref "U$5") (pin "3") (pinfunction "GND_3") (pintype "bidirectional"))
      (node (ref "U$5") (pin "4") (pinfunction "GND_4") (pintype "bidirectional"))
      (node (ref "U$5") (pin "5") (pinfunction "GND_5") (pintype "bidirectional"))
      (node (ref "U$5") (pin "6") (pinfunction "GND_6") (pintype "bidirectional"))
      (node (ref "U$5") (pin "7") (pinfunction "GND_7") (pintype "bidirectional"))
      (node (ref "U$5") (pin "8") (pinfunction "GND_8") (pintype "bidirectional"))
      (node (ref "U$6") (pin "3") (pinfunction "GND_3") (pintype "bidirectional"))
      (node (ref "U$6") (pin "4") (pinfunction "GND_4") (pintype "bidirectional"))
      (node (ref "U$6") (pin "5") (pinfunction "GND_5") (pintype "bidirectional"))
      (node (ref "U$6") (pin "6") (pinfunction "GND_6") (pintype "bidirectional"))
      (node (ref "U$6") (pin "7") (pinfunction "GND_7") (pintype "bidirectional"))
      (node (ref "U$6") (pin "8") (pinfunction "GND_8") (pintype "bidirectional"))
      (node (ref "U$7") (pin "3") (pinfunction "GND_3") (pintype "bidirectional"))
      (node (ref "U$7") (pin "4") (pinfunction "GND_4") (pintype "bidirectional"))
      (node (ref "U$7") (pin "5") (pinfunction "GND_5") (pintype "bidirectional"))
      (node (ref "U$7") (pin "6") (pinfunction "GND_6") (pintype "bidirectional"))
      (node (ref "U$7") (pin "7") (pinfunction "GND_7") (pintype "bidirectional"))
      (node (ref "U$7") (pin "8") (pinfunction "GND_8") (pintype "bidirectional"))
      (node (ref "U$8") (pin "3") (pinfunction "GND_3") (pintype "bidirectional"))
      (node (ref "U$8") (pin "4") (pinfunction "GND_4") (pintype "bidirectional"))
      (node (ref "U$8") (pin "5") (pinfunction "GND_5") (pintype "bidirectional"))
      (node (ref "U$8") (pin "6") (pinfunction "GND_6") (pintype "bidirectional"))
      (node (ref "U$8") (pin "7") (pinfunction "GND_7") (pintype "bidirectional"))
      (node (ref "U$8") (pin "8") (pinfunction "GND_8") (pintype "bidirectional"))
      (node (ref "U$9") (pin "3") (pinfunction "GND_3") (pintype "bidirectional"))
      (node (ref "U$9") (pin "4") (pinfunction "GND_4") (pintype "bidirectional"))
      (node (ref "U$9") (pin "5") (pinfunction "GND_5") (pintype "bidirectional"))
      (node (ref "U$9") (pin "6") (pinfunction "GND_6") (pintype "bidirectional"))
      (node (ref "U$9") (pin "7") (pinfunction "GND_7") (pintype "bidirectional"))
      (node (ref "U$9") (pin "8") (pinfunction "GND_8") (pintype "bidirectional"))
    )
    (net (code "7") (name "Net-(D1-Pad+)") (class "Default")
      (node (ref "D1") (pin "+") (pinfunction "+_+") (pintype "passive"))
      (node (ref "R1") (pin "2") (pinfunction "2_2") (pintype "bidirectional"))
    )
    (net (code "8") (name "Net-(D2-Pad+)") (class "Default")
      (node (ref "D2") (pin "+") (pinfunction "+_+") (pintype "passive"))
      (node (ref "R2") (pin "2") (pinfunction "2_2") (pintype "bidirectional"))
    )
    (net (code "9") (name "Net-(D3-Pad+)") (class "Default")
      (node (ref "D3") (pin "+") (pinfunction "+_+") (pintype "passive"))
      (node (ref "R3") (pin "2") (pinfunction "2_2") (pintype "bidirectional"))
    )
  )
)
